# LPCB235_-_RM48_-_POWER.net
KiCad netlist of a schematic drawn in Altium Designer
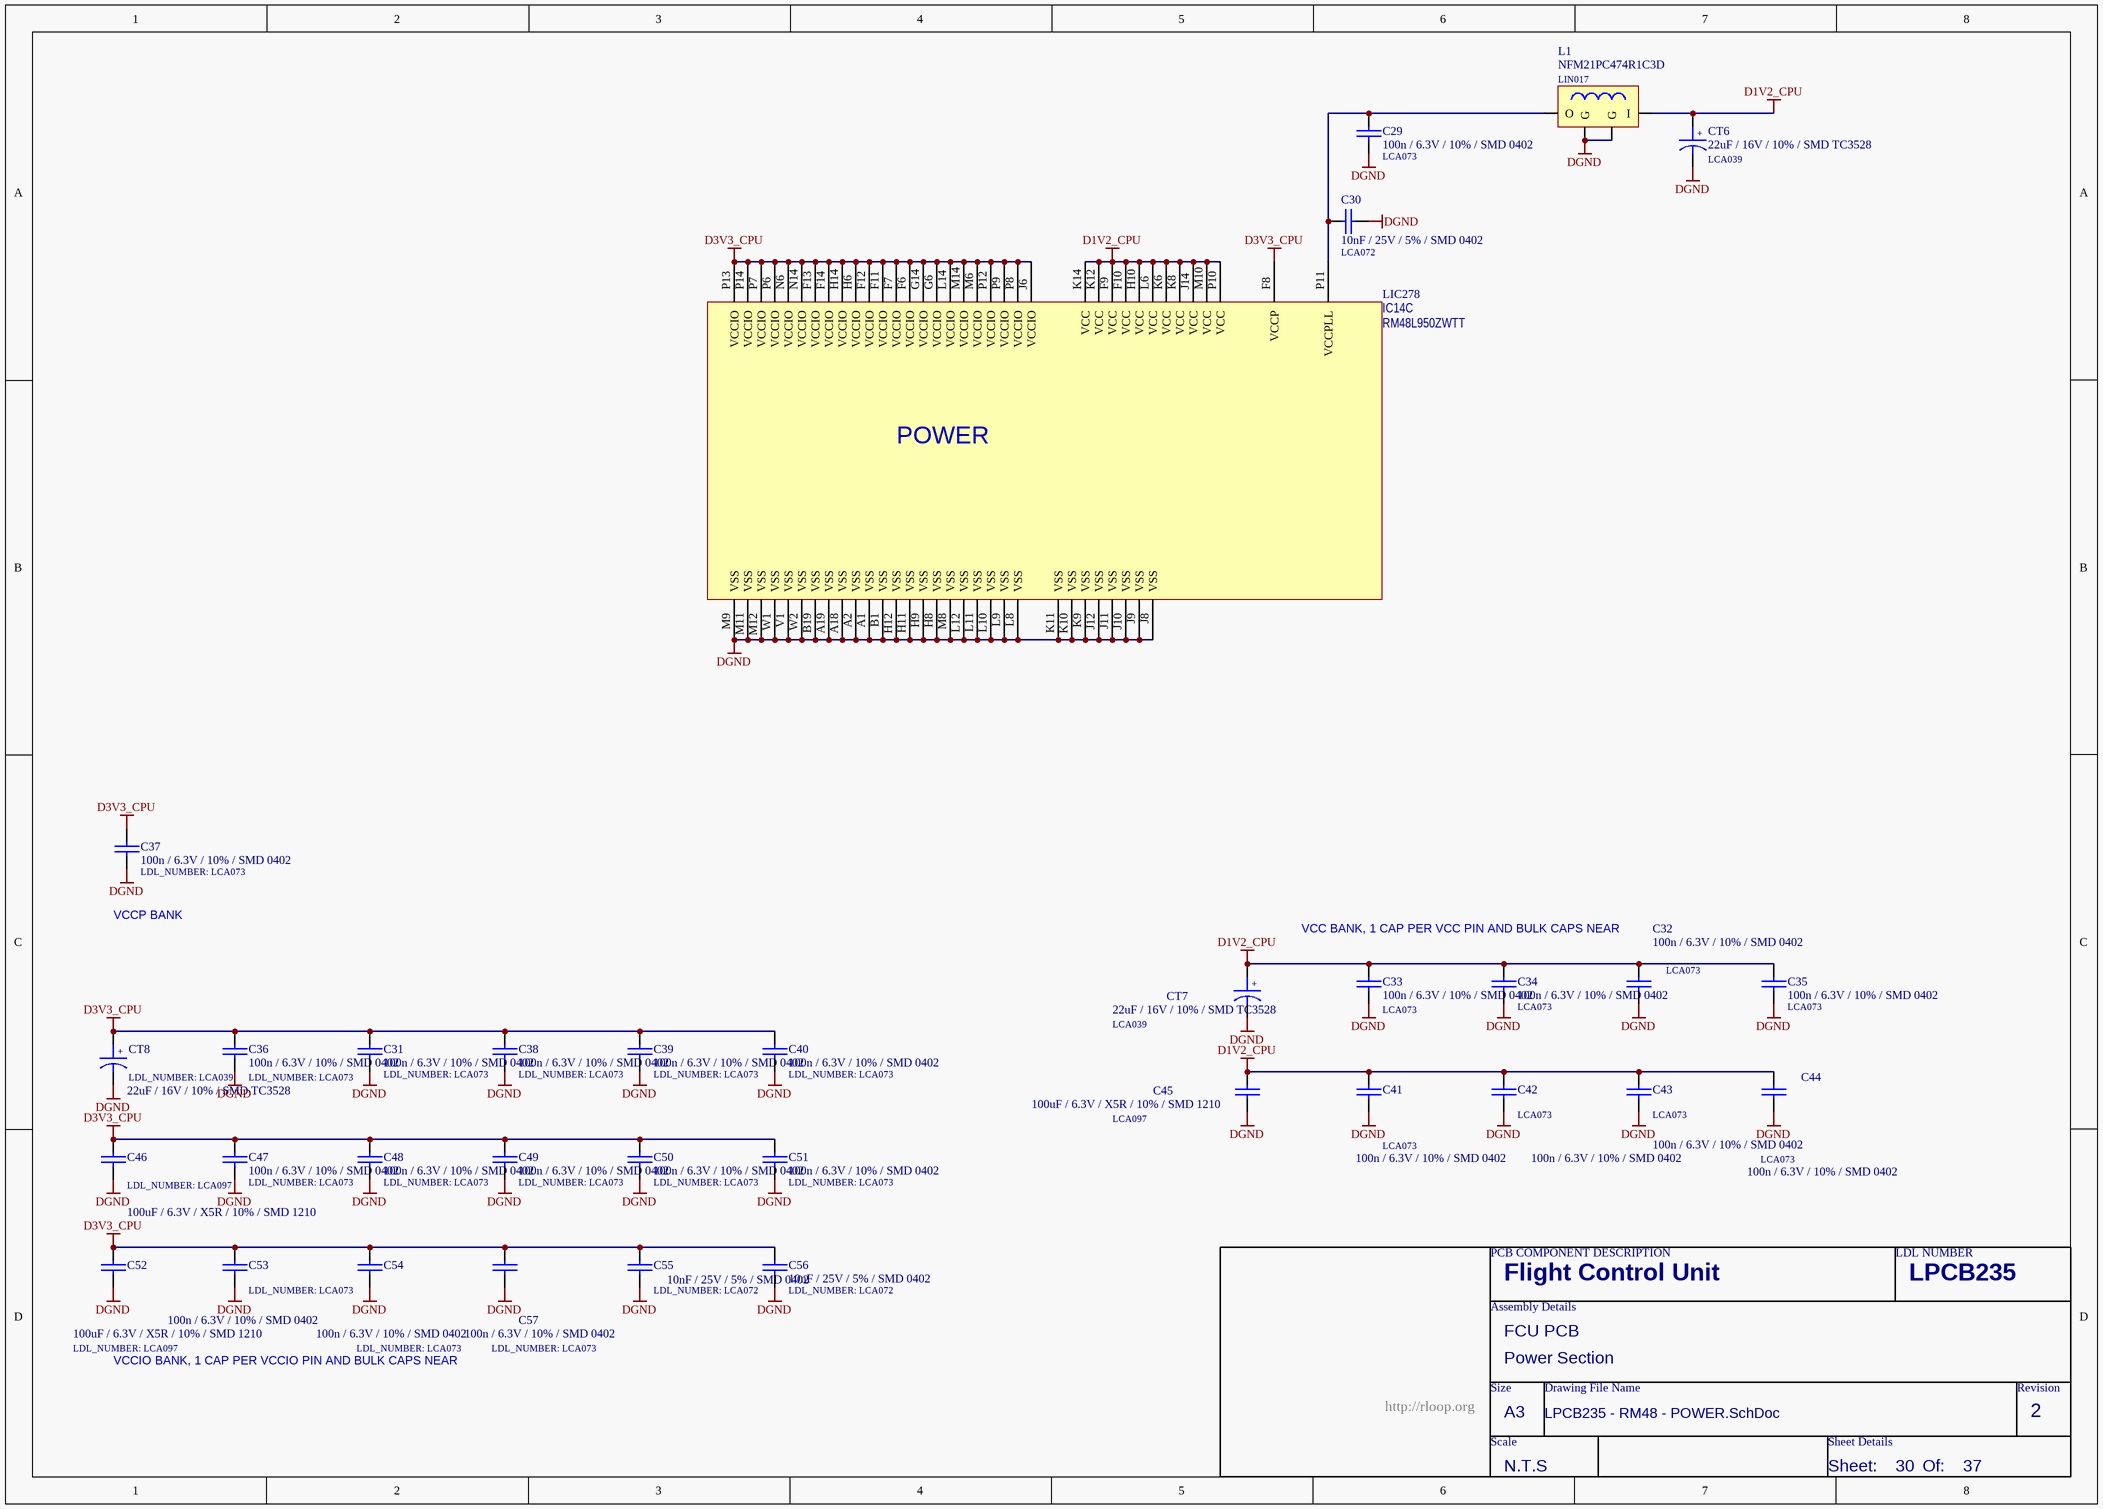
[diagram p0: LPCB235 - RM48 - POWER.SchDoc]

(export (version "E")
  (design (tool "Eeschema 10.0.6"))
  (components
    (comp (ref "C29")
      (value "100n / 6.3V / 10% / SMD 0402")
      (footprint "LFP012__CC1005-0402-IPC7351_B")
      (description "Capacitor, Ceramic Chip, 100nF (0.1uF), 6.3V, 10%, SMD 0402 [LCA073]")
      (fields (field (name "LDL_NUMBER") "LCA073"))
      (libsource (lib "LDL_Capacitors") (part "100n / 6.3V / 10% / SMD 0402"))
    )
    (comp (ref "C30")
      (value "10nF / 25V / 5% / SMD 0402")
      (footprint "LFP012__CC1005-0402-IPC7351_B")
      (description "Capacitor, Ceramic Chip, 10nF (0.01uF), 25V, 5%, SMD 0402 [LCA072]")
      (fields (field (name "LDL_NUMBER") "LCA072"))
      (libsource (lib "LDL_Capacitors") (part "10nF / 25V / 5% / SMD 0402"))
    )
    (comp (ref "C31")
      (value "100n / 6.3V / 10% / SMD 0402")
      (footprint "LFP012__CC1005-0402-IPC7351_B")
      (description "Capacitor, Ceramic Chip, 100nF (0.1uF), 6.3V, 10%, SMD 0402 [LCA073]")
      (fields (field (name "LDL_NUMBER") "LCA073"))
      (libsource (lib "LDL_Capacitors") (part "100n / 6.3V / 10% / SMD 0402"))
    )
    (comp (ref "C32")
      (value "100n / 6.3V / 10% / SMD 0402")
      (footprint "LFP012__CC1005-0402-IPC7351_B")
      (description "Capacitor, Ceramic Chip, 100nF (0.1uF), 6.3V, 10%, SMD 0402 [LCA073]")
      (fields (field (name "LDL_NUMBER") "LCA073"))
      (libsource (lib "LDL_Capacitors") (part "100n / 6.3V / 10% / SMD 0402"))
    )
    (comp (ref "C33")
      (value "100n / 6.3V / 10% / SMD 0402")
      (footprint "LFP012__CC1005-0402-IPC7351_B")
      (description "Capacitor, Ceramic Chip, 100nF (0.1uF), 6.3V, 10%, SMD 0402 [LCA073]")
      (fields (field (name "LDL_NUMBER") "LCA073"))
      (libsource (lib "LDL_Capacitors") (part "100n / 6.3V / 10% / SMD 0402"))
    )
    (comp (ref "C34")
      (value "100n / 6.3V / 10% / SMD 0402")
      (footprint "LFP012__CC1005-0402-IPC7351_B")
      (description "Capacitor, Ceramic Chip, 100nF (0.1uF), 6.3V, 10%, SMD 0402 [LCA073]")
      (fields (field (name "LDL_NUMBER") "LCA073"))
      (libsource (lib "LDL_Capacitors") (part "100n / 6.3V / 10% / SMD 0402"))
    )
    (comp (ref "C35")
      (value "100n / 6.3V / 10% / SMD 0402")
      (footprint "LFP012__CC1005-0402-IPC7351_B")
      (description "Capacitor, Ceramic Chip, 100nF (0.1uF), 6.3V, 10%, SMD 0402 [LCA073]")
      (fields (field (name "LDL_NUMBER") "LCA073"))
      (libsource (lib "LDL_Capacitors") (part "100n / 6.3V / 10% / SMD 0402"))
    )
    (comp (ref "C36")
      (value "100n / 6.3V / 10% / SMD 0402")
      (footprint "LFP012__CC1005-0402-IPC7351_B")
      (description "Capacitor, Ceramic Chip, 100nF (0.1uF), 6.3V, 10%, SMD 0402 [LCA073]")
      (fields (field (name "LDL_NUMBER") "LCA073"))
      (libsource (lib "LDL_Capacitors") (part "100n / 6.3V / 10% / SMD 0402"))
    )
    (comp (ref "C37")
      (value "100n / 6.3V / 10% / SMD 0402")
      (footprint "LFP012__CC1005-0402-IPC7351_B")
      (description "Capacitor, Ceramic Chip, 100nF (0.1uF), 6.3V, 10%, SMD 0402 [LCA073]")
      (fields (field (name "LDL_NUMBER") "LCA073"))
      (libsource (lib "LDL_Capacitors") (part "100n / 6.3V / 10% / SMD 0402"))
    )
    (comp (ref "C38")
      (value "100n / 6.3V / 10% / SMD 0402")
      (footprint "LFP012__CC1005-0402-IPC7351_B")
      (description "Capacitor, Ceramic Chip, 100nF (0.1uF), 6.3V, 10%, SMD 0402 [LCA073]")
      (fields (field (name "LDL_NUMBER") "LCA073"))
      (libsource (lib "LDL_Capacitors") (part "100n / 6.3V / 10% / SMD 0402"))
    )
    (comp (ref "C39")
      (value "100n / 6.3V / 10% / SMD 0402")
      (footprint "LFP012__CC1005-0402-IPC7351_B")
      (description "Capacitor, Ceramic Chip, 100nF (0.1uF), 6.3V, 10%, SMD 0402 [LCA073]")
      (fields (field (name "LDL_NUMBER") "LCA073"))
      (libsource (lib "LDL_Capacitors") (part "100n / 6.3V / 10% / SMD 0402"))
    )
    (comp (ref "C40")
      (value "100n / 6.3V / 10% / SMD 0402")
      (footprint "LFP012__CC1005-0402-IPC7351_B")
      (description "Capacitor, Ceramic Chip, 100nF (0.1uF), 6.3V, 10%, SMD 0402 [LCA073]")
      (fields (field (name "LDL_NUMBER") "LCA073"))
      (libsource (lib "LDL_Capacitors") (part "100n / 6.3V / 10% / SMD 0402"))
    )
    (comp (ref "C41")
      (value "100n / 6.3V / 10% / SMD 0402")
      (footprint "LFP012__CC1005-0402-IPC7351_B")
      (description "Capacitor, Ceramic Chip, 100nF (0.1uF), 6.3V, 10%, SMD 0402 [LCA073]")
      (fields (field (name "LDL_NUMBER") "LCA073"))
      (libsource (lib "LDL_Capacitors") (part "100n / 6.3V / 10% / SMD 0402"))
    )
    (comp (ref "C42")
      (value "100n / 6.3V / 10% / SMD 0402")
      (footprint "LFP012__CC1005-0402-IPC7351_B")
      (description "Capacitor, Ceramic Chip, 100nF (0.1uF), 6.3V, 10%, SMD 0402 [LCA073]")
      (fields (field (name "LDL_NUMBER") "LCA073"))
      (libsource (lib "LDL_Capacitors") (part "100n / 6.3V / 10% / SMD 0402"))
    )
    (comp (ref "C43")
      (value "100n / 6.3V / 10% / SMD 0402")
      (footprint "LFP012__CC1005-0402-IPC7351_B")
      (description "Capacitor, Ceramic Chip, 100nF (0.1uF), 6.3V, 10%, SMD 0402 [LCA073]")
      (fields (field (name "LDL_NUMBER") "LCA073"))
      (libsource (lib "LDL_Capacitors") (part "100n / 6.3V / 10% / SMD 0402"))
    )
    (comp (ref "C44")
      (value "100n / 6.3V / 10% / SMD 0402")
      (footprint "LFP012__CC1005-0402-IPC7351_B")
      (description "Capacitor, Ceramic Chip, 100nF (0.1uF), 6.3V, 10%, SMD 0402 [LCA073]")
      (fields (field (name "LDL_NUMBER") "LCA073"))
      (libsource (lib "LDL_Capacitors") (part "100n / 6.3V / 10% / SMD 0402"))
    )
    (comp (ref "C45")
      (value "100uF / 6.3V / X5R / 10% / SMD 1210")
      (footprint "LFP013__CC3225-1210-IPC7351_B")
      (description "Capacitor, Ceramic Chip, 100uF, 6.3V, X5R, 20%, SMD 1210 [LCA097]")
      (fields (field (name "LDL_NUMBER") "LCA097"))
      (libsource (lib "LDL_Capacitors") (part "100uF / 6.3V / X5R / 10% / SMD 1210"))
    )
    (comp (ref "C46")
      (value "100uF / 6.3V / X5R / 10% / SMD 1210")
      (footprint "LFP013__CC3225-1210-IPC7351_B")
      (description "Capacitor, Ceramic Chip, 100uF, 6.3V, X5R, 20%, SMD 1210 [LCA097]")
      (fields (field (name "LDL_NUMBER") "LCA097"))
      (libsource (lib "LDL_Capacitors") (part "100uF / 6.3V / X5R / 10% / SMD 1210"))
    )
    (comp (ref "C47")
      (value "100n / 6.3V / 10% / SMD 0402")
      (footprint "LFP012__CC1005-0402-IPC7351_B")
      (description "Capacitor, Ceramic Chip, 100nF (0.1uF), 6.3V, 10%, SMD 0402 [LCA073]")
      (fields (field (name "LDL_NUMBER") "LCA073"))
      (libsource (lib "LDL_Capacitors") (part "100n / 6.3V / 10% / SMD 0402"))
    )
    (comp (ref "C48")
      (value "100n / 6.3V / 10% / SMD 0402")
      (footprint "LFP012__CC1005-0402-IPC7351_B")
      (description "Capacitor, Ceramic Chip, 100nF (0.1uF), 6.3V, 10%, SMD 0402 [LCA073]")
      (fields (field (name "LDL_NUMBER") "LCA073"))
      (libsource (lib "LDL_Capacitors") (part "100n / 6.3V / 10% / SMD 0402"))
    )
    (comp (ref "C49")
      (value "100n / 6.3V / 10% / SMD 0402")
      (footprint "LFP012__CC1005-0402-IPC7351_B")
      (description "Capacitor, Ceramic Chip, 100nF (0.1uF), 6.3V, 10%, SMD 0402 [LCA073]")
      (fields (field (name "LDL_NUMBER") "LCA073"))
      (libsource (lib "LDL_Capacitors") (part "100n / 6.3V / 10% / SMD 0402"))
    )
    (comp (ref "C50")
      (value "100n / 6.3V / 10% / SMD 0402")
      (footprint "LFP012__CC1005-0402-IPC7351_B")
      (description "Capacitor, Ceramic Chip, 100nF (0.1uF), 6.3V, 10%, SMD 0402 [LCA073]")
      (fields (field (name "LDL_NUMBER") "LCA073"))
      (libsource (lib "LDL_Capacitors") (part "100n / 6.3V / 10% / SMD 0402"))
    )
    (comp (ref "C51")
      (value "100n / 6.3V / 10% / SMD 0402")
      (footprint "LFP012__CC1005-0402-IPC7351_B")
      (description "Capacitor, Ceramic Chip, 100nF (0.1uF), 6.3V, 10%, SMD 0402 [LCA073]")
      (fields (field (name "LDL_NUMBER") "LCA073"))
      (libsource (lib "LDL_Capacitors") (part "100n / 6.3V / 10% / SMD 0402"))
    )
    (comp (ref "C52")
      (value "100uF / 6.3V / X5R / 10% / SMD 1210")
      (footprint "LFP013__CC3225-1210-IPC7351_B")
      (description "Capacitor, Ceramic Chip, 100uF, 6.3V, X5R, 20%, SMD 1210 [LCA097]")
      (fields (field (name "LDL_NUMBER") "LCA097"))
      (libsource (lib "LDL_Capacitors") (part "100uF / 6.3V / X5R / 10% / SMD 1210"))
    )
    (comp (ref "C53")
      (value "100n / 6.3V / 10% / SMD 0402")
      (footprint "LFP012__CC1005-0402-IPC7351_B")
      (description "Capacitor, Ceramic Chip, 100nF (0.1uF), 6.3V, 10%, SMD 0402 [LCA073]")
      (fields (field (name "LDL_NUMBER") "LCA073"))
      (libsource (lib "LDL_Capacitors") (part "100n / 6.3V / 10% / SMD 0402"))
    )
    (comp (ref "C54")
      (value "100n / 6.3V / 10% / SMD 0402")
      (footprint "LFP012__CC1005-0402-IPC7351_B")
      (description "Capacitor, Ceramic Chip, 100nF (0.1uF), 6.3V, 10%, SMD 0402 [LCA073]")
      (fields (field (name "LDL_NUMBER") "LCA073"))
      (libsource (lib "LDL_Capacitors") (part "100n / 6.3V / 10% / SMD 0402"))
    )
    (comp (ref "C55")
      (value "10nF / 25V / 5% / SMD 0402")
      (footprint "LFP012__CC1005-0402-IPC7351_B")
      (description "Capacitor, Ceramic Chip, 10nF (0.01uF), 25V, 5%, SMD 0402 [LCA072]")
      (fields (field (name "LDL_NUMBER") "LCA072"))
      (libsource (lib "LDL_Capacitors") (part "10nF / 25V / 5% / SMD 0402"))
    )
    (comp (ref "C56")
      (value "10nF / 25V / 5% / SMD 0402")
      (footprint "LFP012__CC1005-0402-IPC7351_B")
      (description "Capacitor, Ceramic Chip, 10nF (0.01uF), 25V, 5%, SMD 0402 [LCA072]")
      (fields (field (name "LDL_NUMBER") "LCA072"))
      (libsource (lib "LDL_Capacitors") (part "10nF / 25V / 5% / SMD 0402"))
    )
    (comp (ref "C57")
      (value "100n / 6.3V / 10% / SMD 0402")
      (footprint "LFP012__CC1005-0402-IPC7351_B")
      (description "Capacitor, Ceramic Chip, 100nF (0.1uF), 6.3V, 10%, SMD 0402 [LCA073]")
      (fields (field (name "LDL_NUMBER") "LCA073"))
      (libsource (lib "LDL_Capacitors") (part "100n / 6.3V / 10% / SMD 0402"))
    )
    (comp (ref "CT6")
      (value "22uF / 16V / 10% / SMD TC3528")
      (footprint "LFP018__TC3528")
      (description "Capacitor, Tantalum, 22uF, 16V, 10%, SMD TC3528 (BCASE) [LCA039]")
      (fields (field (name "LDL_NUMBER") "LCA039"))
      (libsource (lib "LDL_Capacitors") (part "22uF / 16V / 10% / SMD TC3528"))
    )
    (comp (ref "CT7")
      (value "22uF / 16V / 10% / SMD TC3528")
      (footprint "LFP018__TC3528")
      (description "Capacitor, Tantalum, 22uF, 16V, 10%, SMD TC3528 (BCASE) [LCA039]")
      (fields (field (name "LDL_NUMBER") "LCA039"))
      (libsource (lib "LDL_Capacitors") (part "22uF / 16V / 10% / SMD TC3528"))
    )
    (comp (ref "CT8")
      (value "22uF / 16V / 10% / SMD TC3528")
      (footprint "LFP018__TC3528")
      (description "Capacitor, Tantalum, 22uF, 16V, 10%, SMD TC3528 (BCASE) [LCA039]")
      (fields (field (name "LDL_NUMBER") "LCA039"))
      (libsource (lib "LDL_Capacitors") (part "22uF / 16V / 10% / SMD TC3528"))
    )
    (comp (ref "IC14")
      (value "RM48L950ZWTT")
      (footprint "LFP054__ZWT (S-PBGA-N337)")
      (description "IC, CPU, RM48 Safety CPU, SMD NFBGA337 [LIC278]")
      (fields (field (name "LDL_NUMBER") "LIC278"))
      (libsource (lib "LDL_Semiconductors") (part "RM48L950ZWTT"))
    )
    (comp (ref "L1")
      (value "NFM21PC474R1C3D")
      (footprint "LFP117__NFM21P")
      (description "Ferrite, EMI/RFI Suppression, SMD 0805 [LIN017]")
      (fields (field (name "LDL_NUMBER") "LIN017"))
      (libsource (lib "LDL_Inductors") (part "NFM21PC474R1C3D"))
    )
  )
  (nets
    (net (code "1") (name "D1V2_CPU") (class "Default")
      (node (ref "C32") (pin "1") (pintype "passive"))
      (node (ref "C33") (pin "1") (pintype "passive"))
      (node (ref "C34") (pin "1") (pintype "passive"))
      (node (ref "C35") (pin "1") (pintype "passive"))
      (node (ref "C41") (pin "1") (pintype "passive"))
      (node (ref "C42") (pin "1") (pintype "passive"))
      (node (ref "C43") (pin "1") (pintype "passive"))
      (node (ref "C44") (pin "1") (pintype "passive"))
      (node (ref "C45") (pin "1") (pintype "passive"))
      (node (ref "CT6") (pin "1") (pinfunction "1_1") (pintype "passive"))
      (node (ref "CT7") (pin "1") (pinfunction "1_1") (pintype "passive"))
      (node (ref "IC14") (pin "F10") (pinfunction "VCC_F10") (pintype "passive"))
      (node (ref "IC14") (pin "F9") (pinfunction "VCC_F9") (pintype "passive"))
      (node (ref "IC14") (pin "H10") (pinfunction "VCC_H10") (pintype "passive"))
      (node (ref "IC14") (pin "J14") (pinfunction "VCC_J14") (pintype "passive"))
      (node (ref "IC14") (pin "K12") (pinfunction "VCC_K12") (pintype "passive"))
      (node (ref "IC14") (pin "K14") (pinfunction "VCC_K14") (pintype "passive"))
      (node (ref "IC14") (pin "K6") (pinfunction "VCC_K6") (pintype "passive"))
      (node (ref "IC14") (pin "K8") (pinfunction "VCC_K8") (pintype "passive"))
      (node (ref "IC14") (pin "L6") (pinfunction "VCC_L6") (pintype "passive"))
      (node (ref "IC14") (pin "M10") (pinfunction "VCC_M10") (pintype "passive"))
      (node (ref "IC14") (pin "P10") (pinfunction "VCC_P10") (pintype "passive"))
      (node (ref "L1") (pin "1") (pinfunction "I_1") (pintype "passive"))
    )
    (net (code "2") (name "D3V3_CPU") (class "Default")
      (node (ref "C31") (pin "1") (pintype "passive"))
      (node (ref "C36") (pin "1") (pintype "passive"))
      (node (ref "C37") (pin "1") (pintype "passive"))
      (node (ref "C38") (pin "1") (pintype "passive"))
      (node (ref "C39") (pin "1") (pintype "passive"))
      (node (ref "C40") (pin "1") (pintype "passive"))
      (node (ref "C46") (pin "1") (pintype "passive"))
      (node (ref "C47") (pin "1") (pintype "passive"))
      (node (ref "C48") (pin "1") (pintype "passive"))
      (node (ref "C49") (pin "1") (pintype "passive"))
      (node (ref "C50") (pin "1") (pintype "passive"))
      (node (ref "C51") (pin "1") (pintype "passive"))
      (node (ref "C52") (pin "1") (pintype "passive"))
      (node (ref "C53") (pin "1") (pintype "passive"))
      (node (ref "C54") (pin "1") (pintype "passive"))
      (node (ref "C55") (pin "1") (pintype "passive"))
      (node (ref "C56") (pin "1") (pintype "passive"))
      (node (ref "C57") (pin "1") (pintype "passive"))
      (node (ref "CT8") (pin "1") (pinfunction "1_1") (pintype "passive"))
      (node (ref "IC14") (pin "F11") (pinfunction "VCCIO_F11") (pintype "passive"))
      (node (ref "IC14") (pin "F12") (pinfunction "VCCIO_F12") (pintype "passive"))
      (node (ref "IC14") (pin "F13") (pinfunction "VCCIO_F13") (pintype "passive"))
      (node (ref "IC14") (pin "F14") (pinfunction "VCCIO_F14") (pintype "passive"))
      (node (ref "IC14") (pin "F6") (pinfunction "VCCIO_F6") (pintype "passive"))
      (node (ref "IC14") (pin "F7") (pinfunction "VCCIO_F7") (pintype "passive"))
      (node (ref "IC14") (pin "F8") (pinfunction "VCCP_F8") (pintype "passive"))
      (node (ref "IC14") (pin "G14") (pinfunction "VCCIO_G14") (pintype "passive"))
      (node (ref "IC14") (pin "G6") (pinfunction "VCCIO_G6") (pintype "passive"))
      (node (ref "IC14") (pin "H14") (pinfunction "VCCIO_H14") (pintype "passive"))
      (node (ref "IC14") (pin "H6") (pinfunction "VCCIO_H6") (pintype "passive"))
      (node (ref "IC14") (pin "J6") (pinfunction "VCCIO_J6") (pintype "passive"))
      (node (ref "IC14") (pin "L14") (pinfunction "VCCIO_L14") (pintype "passive"))
      (node (ref "IC14") (pin "M14") (pinfunction "VCCIO_M14") (pintype "passive"))
      (node (ref "IC14") (pin "M6") (pinfunction "VCCIO_M6") (pintype "passive"))
      (node (ref "IC14") (pin "N14") (pinfunction "VCCIO_N14") (pintype "passive"))
      (node (ref "IC14") (pin "N6") (pinfunction "VCCIO_N6") (pintype "passive"))
      (node (ref "IC14") (pin "P12") (pinfunction "VCCIO_P12") (pintype "passive"))
      (node (ref "IC14") (pin "P13") (pinfunction "VCCIO_P13") (pintype "passive"))
      (node (ref "IC14") (pin "P14") (pinfunction "VCCIO_P14") (pintype "passive"))
      (node (ref "IC14") (pin "P6") (pinfunction "VCCIO_P6") (pintype "passive"))
      (node (ref "IC14") (pin "P7") (pinfunction "VCCIO_P7") (pintype "passive"))
      (node (ref "IC14") (pin "P8") (pinfunction "VCCIO_P8") (pintype "passive"))
      (node (ref "IC14") (pin "P9") (pinfunction "VCCIO_P9") (pintype "passive"))
    )
    (net (code "3") (name "DGND") (class "Default")
      (node (ref "C29") (pin "2") (pintype "passive"))
      (node (ref "C30") (pin "2") (pintype "passive"))
      (node (ref "C31") (pin "2") (pintype "passive"))
      (node (ref "C32") (pin "2") (pintype "passive"))
      (node (ref "C33") (pin "2") (pintype "passive"))
      (node (ref "C34") (pin "2") (pintype "passive"))
      (node (ref "C35") (pin "2") (pintype "passive"))
      (node (ref "C36") (pin "2") (pintype "passive"))
      (node (ref "C37") (pin "2") (pintype "passive"))
      (node (ref "C38") (pin "2") (pintype "passive"))
      (node (ref "C39") (pin "2") (pintype "passive"))
      (node (ref "C40") (pin "2") (pintype "passive"))
      (node (ref "C41") (pin "2") (pintype "passive"))
      (node (ref "C42") (pin "2") (pintype "passive"))
      (node (ref "C43") (pin "2") (pintype "passive"))
      (node (ref "C44") (pin "2") (pintype "passive"))
      (node (ref "C45") (pin "2") (pintype "passive"))
      (node (ref "C46") (pin "2") (pintype "passive"))
      (node (ref "C47") (pin "2") (pintype "passive"))
      (node (ref "C48") (pin "2") (pintype "passive"))
      (node (ref "C49") (pin "2") (pintype "passive"))
      (node (ref "C50") (pin "2") (pintype "passive"))
      (node (ref "C51") (pin "2") (pintype "passive"))
      (node (ref "C52") (pin "2") (pintype "passive"))
      (node (ref "C53") (pin "2") (pintype "passive"))
      (node (ref "C54") (pin "2") (pintype "passive"))
      (node (ref "C55") (pin "2") (pintype "passive"))
      (node (ref "C56") (pin "2") (pintype "passive"))
      (node (ref "C57") (pin "2") (pintype "passive"))
      (node (ref "CT6") (pin "2") (pinfunction "2_2") (pintype "passive"))
      (node (ref "CT7") (pin "2") (pinfunction "2_2") (pintype "passive"))
      (node (ref "CT8") (pin "2") (pinfunction "2_2") (pintype "passive"))
      (node (ref "IC14") (pin "A1") (pinfunction "VSS_A1") (pintype "passive"))
      (node (ref "IC14") (pin "A18") (pinfunction "VSS_A18") (pintype "passive"))
      (node (ref "IC14") (pin "A19") (pinfunction "VSS_A19") (pintype "passive"))
      (node (ref "IC14") (pin "A2") (pinfunction "VSS_A2") (pintype "passive"))
      (node (ref "IC14") (pin "B1") (pinfunction "VSS_B1") (pintype "passive"))
      (node (ref "IC14") (pin "B19") (pinfunction "VSS_B19") (pintype "passive"))
      (node (ref "IC14") (pin "H11") (pinfunction "VSS_H11") (pintype "passive"))
      (node (ref "IC14") (pin "H12") (pinfunction "VSS_H12") (pintype "passive"))
      (node (ref "IC14") (pin "H8") (pinfunction "VSS_H8") (pintype "passive"))
      (node (ref "IC14") (pin "H9") (pinfunction "VSS_H9") (pintype "passive"))
      (node (ref "IC14") (pin "J10") (pinfunction "VSS_J10") (pintype "passive"))
      (node (ref "IC14") (pin "J11") (pinfunction "VSS_J11") (pintype "passive"))
      (node (ref "IC14") (pin "J12") (pinfunction "VSS_J12") (pintype "passive"))
      (node (ref "IC14") (pin "J8") (pinfunction "VSS_J8") (pintype "passive"))
      (node (ref "IC14") (pin "J9") (pinfunction "VSS_J9") (pintype "passive"))
      (node (ref "IC14") (pin "K10") (pinfunction "VSS_K10") (pintype "passive"))
      (node (ref "IC14") (pin "K11") (pinfunction "VSS_K11") (pintype "passive"))
      (node (ref "IC14") (pin "K9") (pinfunction "VSS_K9") (pintype "passive"))
      (node (ref "IC14") (pin "L10") (pinfunction "VSS_L10") (pintype "passive"))
      (node (ref "IC14") (pin "L11") (pinfunction "VSS_L11") (pintype "passive"))
      (node (ref "IC14") (pin "L12") (pinfunction "VSS_L12") (pintype "passive"))
      (node (ref "IC14") (pin "L8") (pinfunction "VSS_L8") (pintype "passive"))
      (node (ref "IC14") (pin "L9") (pinfunction "VSS_L9") (pintype "passive"))
      (node (ref "IC14") (pin "M11") (pinfunction "VSS_M11") (pintype "passive"))
      (node (ref "IC14") (pin "M12") (pinfunction "VSS_M12") (pintype "passive"))
      (node (ref "IC14") (pin "M8") (pinfunction "VSS_M8") (pintype "passive"))
      (node (ref "IC14") (pin "M9") (pinfunction "VSS_M9") (pintype "passive"))
      (node (ref "IC14") (pin "V1") (pinfunction "VSS_V1") (pintype "passive"))
      (node (ref "IC14") (pin "W1") (pinfunction "VSS_W1") (pintype "passive"))
      (node (ref "IC14") (pin "W2") (pinfunction "VSS_W2") (pintype "passive"))
      (node (ref "L1") (pin "G1") (pinfunction "G_G1") (pintype "passive"))
      (node (ref "L1") (pin "G2") (pinfunction "G_G2") (pintype "passive"))
    )
    (net (code "4") (name "Net-(IC14C-VCCPLL)") (class "Default")
      (node (ref "C29") (pin "1") (pintype "passive"))
      (node (ref "C30") (pin "1") (pintype "passive"))
      (node (ref "IC14") (pin "P11") (pinfunction "VCCPLL_P11") (pintype "passive"))
      (node (ref "L1") (pin "2") (pinfunction "O_2") (pintype "passive"))
    )
  )
)
